# stm32f4stampV1_3.net
KiCad netlist of a schematic drawn in EAGLE
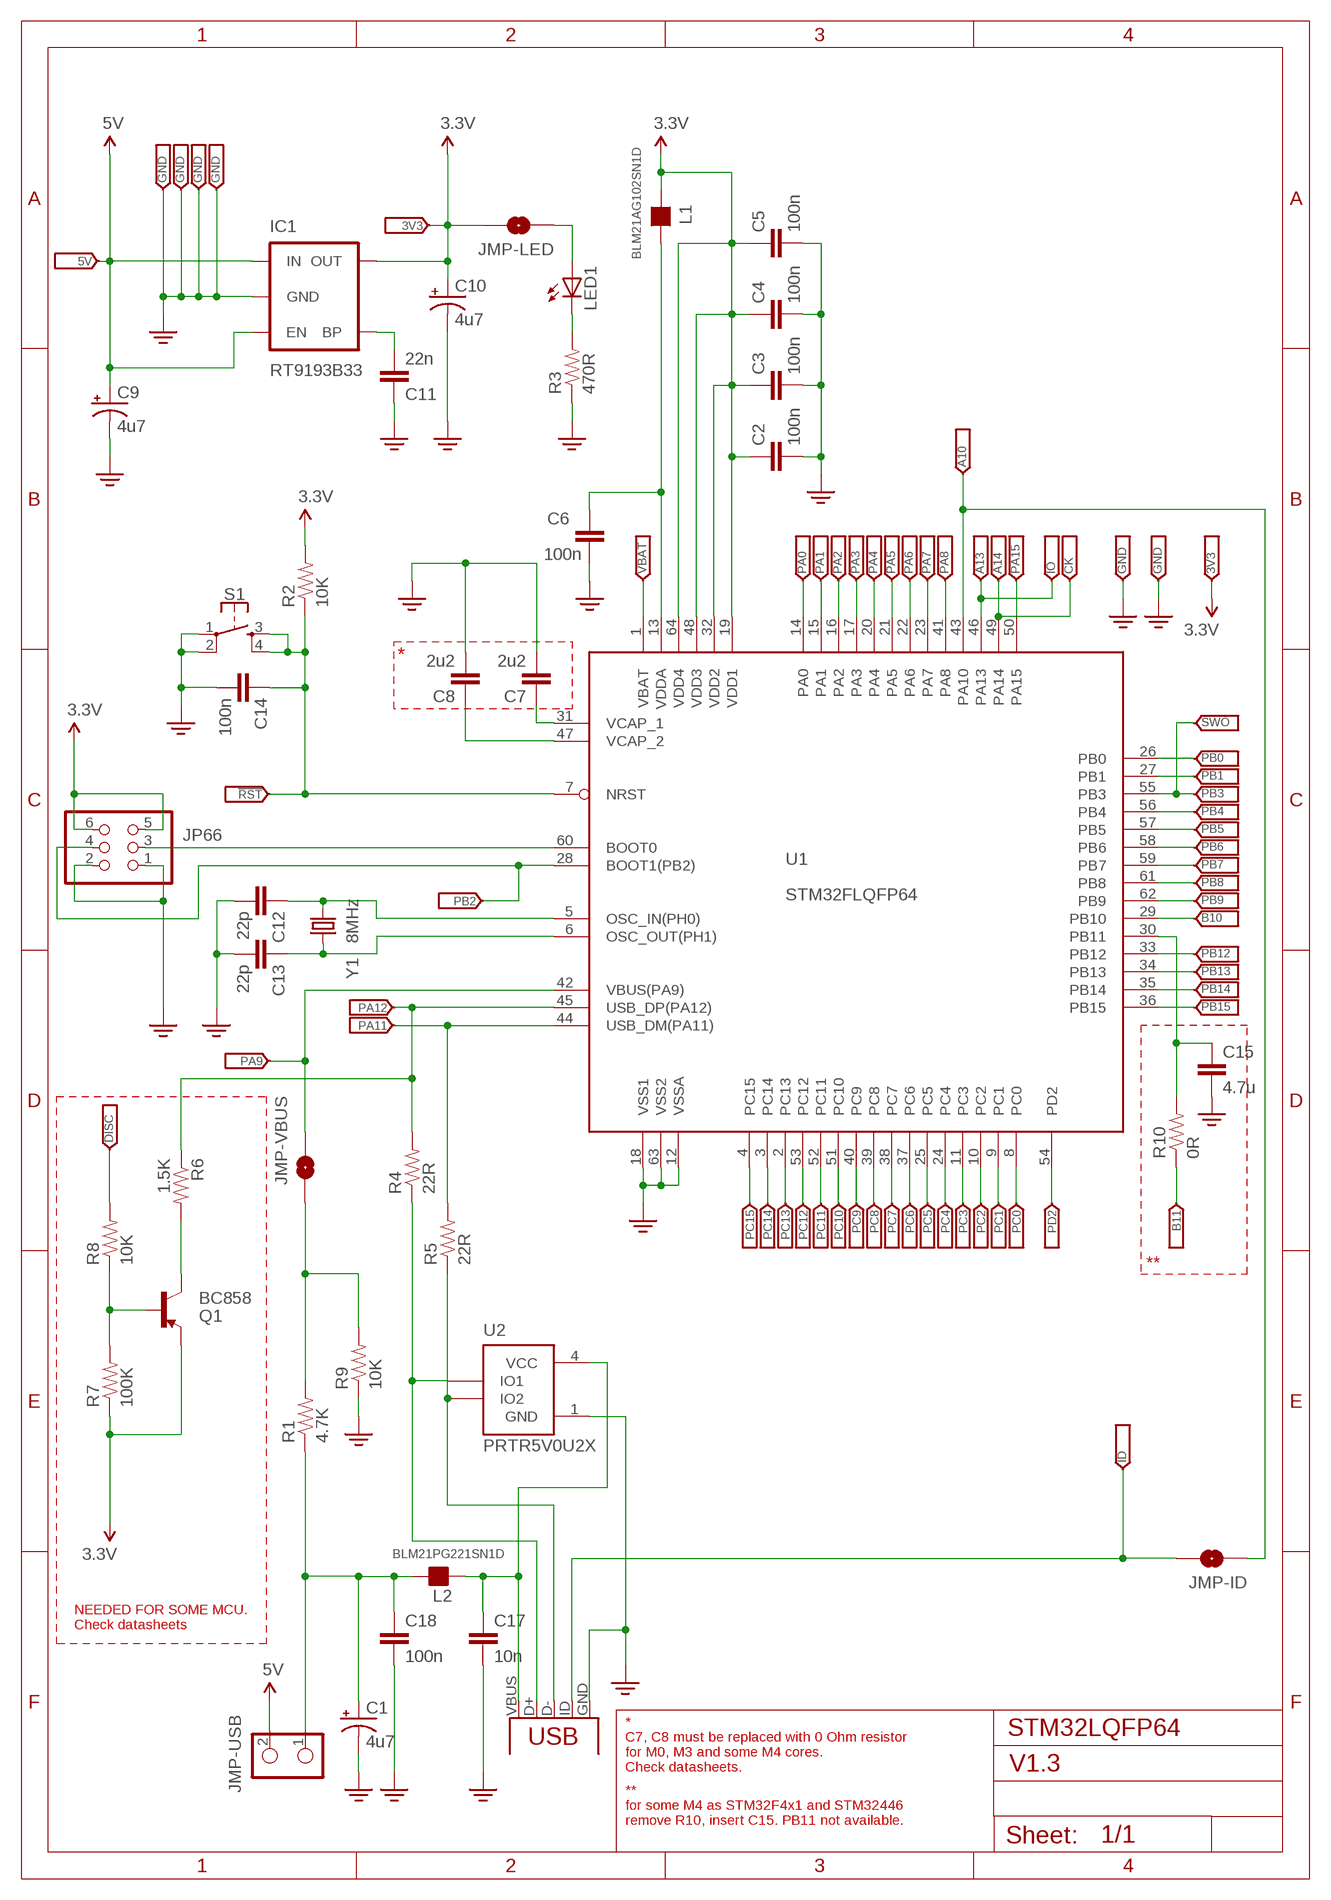
[diagram p0: schematic, sheet 1]

(export (version "E")
  (design (tool "Eeschema 10.0.6"))
  (components
    (comp (ref "C1")
      (value "4u7")
      (footprint "eagle-import:EIA3216-KIT")
      (libsource (lib "eagle-import") (part "CAP_POL1206-KIT"))
    )
    (comp (ref "C2")
      (value "100n")
      (footprint "eagle-import:0805")
      (libsource (lib "eagle-import") (part "CAP0805"))
    )
    (comp (ref "C3")
      (value "100n")
      (footprint "eagle-import:0805")
      (libsource (lib "eagle-import") (part "CAP0805"))
    )
    (comp (ref "C4")
      (value "100n")
      (footprint "eagle-import:0805")
      (libsource (lib "eagle-import") (part "CAP0805"))
    )
    (comp (ref "C5")
      (value "100n")
      (footprint "eagle-import:0805")
      (libsource (lib "eagle-import") (part "CAP0805"))
    )
    (comp (ref "C6")
      (value "100n")
      (footprint "eagle-import:0805")
      (libsource (lib "eagle-import") (part "CAP0805"))
    )
    (comp (ref "C7")
      (value "2u2")
      (footprint "eagle-import:0805")
      (libsource (lib "eagle-import") (part "CAP0805"))
    )
    (comp (ref "C8")
      (value "2u2")
      (footprint "eagle-import:0805")
      (libsource (lib "eagle-import") (part "CAP0805"))
    )
    (comp (ref "C9")
      (value "4u7")
      (footprint "eagle-import:EIA3216-KIT")
      (libsource (lib "eagle-import") (part "CAP_POL1206-KIT"))
    )
    (comp (ref "C10")
      (value "4u7")
      (footprint "eagle-import:EIA3216-KIT")
      (libsource (lib "eagle-import") (part "CAP_POL1206-KIT"))
    )
    (comp (ref "C11")
      (value "22n")
      (footprint "eagle-import:0805")
      (libsource (lib "eagle-import") (part "CAP0805"))
    )
    (comp (ref "C12")
      (value "22p")
      (footprint "eagle-import:0805")
      (libsource (lib "eagle-import") (part "CAP0805"))
    )
    (comp (ref "C13")
      (value "22p")
      (footprint "eagle-import:0805")
      (libsource (lib "eagle-import") (part "CAP0805"))
    )
    (comp (ref "C14")
      (value "100n")
      (footprint "eagle-import:0805")
      (libsource (lib "eagle-import") (part "CAP0805"))
    )
    (comp (ref "C15")
      (value "4.7u")
      (footprint "eagle-import:0805")
      (libsource (lib "eagle-import") (part "CAP0805"))
    )
    (comp (ref "C17")
      (value "10n")
      (footprint "eagle-import:0805")
      (libsource (lib "eagle-import") (part "CAP0805"))
    )
    (comp (ref "C18")
      (value "100n")
      (footprint "eagle-import:0805")
      (libsource (lib "eagle-import") (part "CAP0805"))
    )
    (comp (ref "IC1")
      (value "RT9193B33")
      (footprint "eagle-import:SOT23-5")
      (libsource (lib "eagle-import") (part "V_REG_LDOSMD"))
    )
    (comp (ref "JMP-ID")
      (value "SOLDERJUMPERNO")
      (footprint "eagle-import:SJ_2S-NO")
      (libsource (lib "eagle-import") (part "SOLDERJUMPERNO"))
    )
    (comp (ref "JMP-LED")
      (value "SOLDERJUMPERNO")
      (footprint "eagle-import:SJ_2S-NO")
      (libsource (lib "eagle-import") (part "SOLDERJUMPERNO"))
    )
    (comp (ref "JMP-USB")
      (value "JUMPER-2PTH")
      (footprint "eagle-import:1X02")
      (libsource (lib "eagle-import") (part "JUMPER-2PTH"))
    )
    (comp (ref "JMP-VBUS")
      (value "SOLDERJUMPERNO")
      (footprint "eagle-import:SJ_2S-NO")
      (libsource (lib "eagle-import") (part "SOLDERJUMPERNO"))
    )
    (comp (ref "JP1")
      (value "PA12")
      (footprint "eagle-import:1X1-HEADER-HOLE")
      (libsource (lib "eagle-import") (part "HEADERHOLE-HEADERHOLE"))
    )
    (comp (ref "JP2")
      (value "5V")
      (footprint "eagle-import:1X1-HEADER-HOLE")
      (libsource (lib "eagle-import") (part "HEADERHOLE-HEADERHOLE"))
    )
    (comp (ref "JP3")
      (value "GND")
      (footprint "eagle-import:1X1-HEADER-HOLE")
      (libsource (lib "eagle-import") (part "HEADERHOLE-HEADERHOLE"))
    )
    (comp (ref "JP4")
      (value "3V3")
      (footprint "eagle-import:1X1-HEADER-HOLE")
      (libsource (lib "eagle-import") (part "HEADERHOLE-HEADERHOLE"))
    )
    (comp (ref "JP5")
      (value "DISC")
      (footprint "eagle-import:1X1-HEADER-HOLE")
      (libsource (lib "eagle-import") (part "HEADERHOLE-HEADERHOLE"))
    )
    (comp (ref "JP6")
      (value "GND")
      (footprint "eagle-import:1X1-HEADER-HOLE")
      (libsource (lib "eagle-import") (part "HEADERHOLE-HEADERHOLE"))
    )
    (comp (ref "JP7")
      (value "GND")
      (footprint "eagle-import:1X1-HEADER-HOLE")
      (libsource (lib "eagle-import") (part "HEADERHOLE-HEADERHOLE"))
    )
    (comp (ref "JP8")
      (value "PB8")
      (footprint "eagle-import:1X1-HEADER-HOLE")
      (libsource (lib "eagle-import") (part "HEADERHOLE-HEADERHOLE"))
    )
    (comp (ref "JP9")
      (value "A10")
      (footprint "eagle-import:1X1-HEADER-HOLE")
      (libsource (lib "eagle-import") (part "HEADERHOLE-HEADERHOLE"))
    )
    (comp (ref "JP10")
      (value "PA8")
      (footprint "eagle-import:1X1-HEADER-HOLE")
      (libsource (lib "eagle-import") (part "HEADERHOLE-HEADERHOLE"))
    )
    (comp (ref "JP11")
      (value "A13")
      (footprint "eagle-import:1X1-HEADER-HOLE")
      (libsource (lib "eagle-import") (part "HEADERHOLE-HEADERHOLE"))
    )
    (comp (ref "JP12")
      (value "PC9")
      (footprint "eagle-import:1X1-HEADER-HOLE")
      (libsource (lib "eagle-import") (part "HEADERHOLE-HEADERHOLE"))
    )
    (comp (ref "JP13")
      (value "PC15")
      (footprint "eagle-import:1X1-HEADER-HOLE")
      (libsource (lib "eagle-import") (part "HEADERHOLE-HEADERHOLE"))
    )
    (comp (ref "JP14")
      (value "PC14")
      (footprint "eagle-import:1X1-HEADER-HOLE")
      (libsource (lib "eagle-import") (part "HEADERHOLE-HEADERHOLE"))
    )
    (comp (ref "JP15")
      (value "PC13")
      (footprint "eagle-import:1X1-HEADER-HOLE")
      (libsource (lib "eagle-import") (part "HEADERHOLE-HEADERHOLE"))
    )
    (comp (ref "JP16")
      (value "PC12")
      (footprint "eagle-import:1X1-HEADER-HOLE")
      (libsource (lib "eagle-import") (part "HEADERHOLE-HEADERHOLE"))
    )
    (comp (ref "JP17")
      (value "PC11")
      (footprint "eagle-import:1X1-HEADER-HOLE")
      (libsource (lib "eagle-import") (part "HEADERHOLE-HEADERHOLE"))
    )
    (comp (ref "JP18")
      (value "PC10")
      (footprint "eagle-import:1X1-HEADER-HOLE")
      (libsource (lib "eagle-import") (part "HEADERHOLE-HEADERHOLE"))
    )
    (comp (ref "JP19")
      (value "PC8")
      (footprint "eagle-import:1X1-HEADER-HOLE")
      (libsource (lib "eagle-import") (part "HEADERHOLE-HEADERHOLE"))
    )
    (comp (ref "JP20")
      (value "PC7")
      (footprint "eagle-import:1X1-HEADER-HOLE")
      (libsource (lib "eagle-import") (part "HEADERHOLE-HEADERHOLE"))
    )
    (comp (ref "JP21")
      (value "PC6")
      (footprint "eagle-import:1X1-HEADER-HOLE")
      (libsource (lib "eagle-import") (part "HEADERHOLE-HEADERHOLE"))
    )
    (comp (ref "JP22")
      (value "PC5")
      (footprint "eagle-import:1X1-HEADER-HOLE")
      (libsource (lib "eagle-import") (part "HEADERHOLE-HEADERHOLE"))
    )
    (comp (ref "JP23")
      (value "PC4")
      (footprint "eagle-import:1X1-HEADER-HOLE")
      (libsource (lib "eagle-import") (part "HEADERHOLE-HEADERHOLE"))
    )
    (comp (ref "JP24")
      (value "PC3")
      (footprint "eagle-import:1X1-HEADER-HOLE")
      (libsource (lib "eagle-import") (part "HEADERHOLE-HEADERHOLE"))
    )
    (comp (ref "JP25")
      (value "PC2")
      (footprint "eagle-import:1X1-HEADER-HOLE")
      (libsource (lib "eagle-import") (part "HEADERHOLE-HEADERHOLE"))
    )
    (comp (ref "JP26")
      (value "PC1")
      (footprint "eagle-import:1X1-HEADER-HOLE")
      (libsource (lib "eagle-import") (part "HEADERHOLE-HEADERHOLE"))
    )
    (comp (ref "JP27")
      (value "PC0")
      (footprint "eagle-import:1X1-HEADER-HOLE")
      (libsource (lib "eagle-import") (part "HEADERHOLE-HEADERHOLE"))
    )
    (comp (ref "JP28")
      (value "PD2")
      (footprint "eagle-import:1X1-HEADER-HOLE")
      (libsource (lib "eagle-import") (part "HEADERHOLE-HEADERHOLE"))
    )
    (comp (ref "JP29")
      (value "PA0")
      (footprint "eagle-import:1X1-HEADER-HOLE")
      (libsource (lib "eagle-import") (part "HEADERHOLE-HEADERHOLE"))
    )
    (comp (ref "JP30")
      (value "PA1")
      (footprint "eagle-import:1X1-HEADER-HOLE")
      (libsource (lib "eagle-import") (part "HEADERHOLE-HEADERHOLE"))
    )
    (comp (ref "JP31")
      (value "PA2")
      (footprint "eagle-import:1X1-HEADER-HOLE")
      (libsource (lib "eagle-import") (part "HEADERHOLE-HEADERHOLE"))
    )
    (comp (ref "JP32")
      (value "PA3")
      (footprint "eagle-import:1X1-HEADER-HOLE")
      (libsource (lib "eagle-import") (part "HEADERHOLE-HEADERHOLE"))
    )
    (comp (ref "JP33")
      (value "PA4")
      (footprint "eagle-import:1X1-HEADER-HOLE")
      (libsource (lib "eagle-import") (part "HEADERHOLE-HEADERHOLE"))
    )
    (comp (ref "JP34")
      (value "PA5")
      (footprint "eagle-import:1X1-HEADER-HOLE")
      (libsource (lib "eagle-import") (part "HEADERHOLE-HEADERHOLE"))
    )
    (comp (ref "JP35")
      (value "PA6")
      (footprint "eagle-import:1X1-HEADER-HOLE")
      (libsource (lib "eagle-import") (part "HEADERHOLE-HEADERHOLE"))
    )
    (comp (ref "JP36")
      (value "PA7")
      (footprint "eagle-import:1X1-HEADER-HOLE")
      (libsource (lib "eagle-import") (part "HEADERHOLE-HEADERHOLE"))
    )
    (comp (ref "JP37")
      (value "A14")
      (footprint "eagle-import:1X1-HEADER-HOLE")
      (libsource (lib "eagle-import") (part "HEADERHOLE-HEADERHOLE"))
    )
    (comp (ref "JP38")
      (value "PA15")
      (footprint "eagle-import:1X1-HEADER-HOLE")
      (libsource (lib "eagle-import") (part "HEADERHOLE-HEADERHOLE"))
    )
    (comp (ref "JP39")
      (value "PB0")
      (footprint "eagle-import:1X1-HEADER-HOLE")
      (libsource (lib "eagle-import") (part "HEADERHOLE-HEADERHOLE"))
    )
    (comp (ref "JP40")
      (value "PB1")
      (footprint "eagle-import:1X1-HEADER-HOLE")
      (libsource (lib "eagle-import") (part "HEADERHOLE-HEADERHOLE"))
    )
    (comp (ref "JP41")
      (value "PB3")
      (footprint "eagle-import:1X1-HEADER-HOLE")
      (libsource (lib "eagle-import") (part "HEADERHOLE-HEADERHOLE"))
    )
    (comp (ref "JP42")
      (value "PB4")
      (footprint "eagle-import:1X1-HEADER-HOLE")
      (libsource (lib "eagle-import") (part "HEADERHOLE-HEADERHOLE"))
    )
    (comp (ref "JP43")
      (value "PB5")
      (footprint "eagle-import:1X1-HEADER-HOLE")
      (libsource (lib "eagle-import") (part "HEADERHOLE-HEADERHOLE"))
    )
    (comp (ref "JP44")
      (value "PB6")
      (footprint "eagle-import:1X1-HEADER-HOLE")
      (libsource (lib "eagle-import") (part "HEADERHOLE-HEADERHOLE"))
    )
    (comp (ref "JP45")
      (value "PB7")
      (footprint "eagle-import:1X1-HEADER-HOLE")
      (libsource (lib "eagle-import") (part "HEADERHOLE-HEADERHOLE"))
    )
    (comp (ref "JP46")
      (value "PB9")
      (footprint "eagle-import:1X1-HEADER-HOLE")
      (libsource (lib "eagle-import") (part "HEADERHOLE-HEADERHOLE"))
    )
    (comp (ref "JP47")
      (value "B10")
      (footprint "eagle-import:1X1-HEADER-HOLE")
      (libsource (lib "eagle-import") (part "HEADERHOLE-HEADERHOLE"))
    )
    (comp (ref "JP48")
      (value "B11")
      (footprint "eagle-import:1X1-HEADER-HOLE")
      (libsource (lib "eagle-import") (part "HEADERHOLE-HEADERHOLE"))
    )
    (comp (ref "JP49")
      (value "PB12")
      (footprint "eagle-import:1X1-HEADER-HOLE")
      (libsource (lib "eagle-import") (part "HEADERHOLE-HEADERHOLE"))
    )
    (comp (ref "JP50")
      (value "PB13")
      (footprint "eagle-import:1X1-HEADER-HOLE")
      (libsource (lib "eagle-import") (part "HEADERHOLE-HEADERHOLE"))
    )
    (comp (ref "JP51")
      (value "PB14")
      (footprint "eagle-import:1X1-HEADER-HOLE")
      (libsource (lib "eagle-import") (part "HEADERHOLE-HEADERHOLE"))
    )
    (comp (ref "JP52")
      (value "PB15")
      (footprint "eagle-import:1X1-HEADER-HOLE")
      (libsource (lib "eagle-import") (part "HEADERHOLE-HEADERHOLE"))
    )
    (comp (ref "JP53")
      (value "VBAT")
      (footprint "eagle-import:1X1-HEADER-HOLE")
      (libsource (lib "eagle-import") (part "HEADERHOLE-HEADERHOLE"))
    )
    (comp (ref "JP54")
      (value "!RST")
      (footprint "eagle-import:1X1-HEADER-HOLE")
      (libsource (lib "eagle-import") (part "HEADERHOLE-HEADERHOLE"))
    )
    (comp (ref "JP55")
      (value "GND")
      (footprint "eagle-import:1X1-HEADER-HOLE")
      (libsource (lib "eagle-import") (part "HEADERHOLE-HEADERHOLE"))
    )
    (comp (ref "JP56")
      (value "ID")
      (footprint "eagle-import:1X1-HEADER-HOLE")
      (libsource (lib "eagle-import") (part "HEADERHOLE-HEADERHOLE"))
    )
    (comp (ref "JP57")
      (value "PB2")
      (footprint "eagle-import:1X1-HEADER-HOLE")
      (libsource (lib "eagle-import") (part "HEADERHOLE-HEADERHOLE"))
    )
    (comp (ref "JP58")
      (value "PA11")
      (footprint "eagle-import:1X1-HEADER-HOLE")
      (libsource (lib "eagle-import") (part "HEADERHOLE-HEADERHOLE"))
    )
    (comp (ref "JP59")
      (value "IO")
      (footprint "eagle-import:1X1-HEADER-HOLE")
      (libsource (lib "eagle-import") (part "HEADERHOLE-HEADERHOLE"))
    )
    (comp (ref "JP60")
      (value "CK")
      (footprint "eagle-import:1X1-HEADER-HOLE")
      (libsource (lib "eagle-import") (part "HEADERHOLE-HEADERHOLE"))
    )
    (comp (ref "JP61")
      (value "SWO")
      (footprint "eagle-import:1X1-HEADER-HOLE")
      (libsource (lib "eagle-import") (part "HEADERHOLE-HEADERHOLE"))
    )
    (comp (ref "JP62")
      (value "GND")
      (footprint "eagle-import:1X1-HEADER-HOLE")
      (libsource (lib "eagle-import") (part "HEADERHOLE-HEADERHOLE"))
    )
    (comp (ref "JP63")
      (value "3V3")
      (footprint "eagle-import:1X1-HEADER-HOLE")
      (libsource (lib "eagle-import") (part "HEADERHOLE-HEADERHOLE"))
    )
    (comp (ref "JP64")
      (value "PA9")
      (footprint "eagle-import:1X1-HEADER-HOLE")
      (libsource (lib "eagle-import") (part "HEADERHOLE-HEADERHOLE"))
    )
    (comp (ref "JP65")
      (value "GND")
      (footprint "eagle-import:1X1-HEADER-HOLE")
      (libsource (lib "eagle-import") (part "HEADERHOLE-HEADERHOLE"))
    )
    (comp (ref "JP66")
      (value "PINHD-2X3")
      (footprint "eagle-import:2X03")
      (libsource (lib "eagle-import") (part "PINHD-2X3"))
    )
    (comp (ref "L1")
      (value "BLM21AG102SN1D")
      (footprint "eagle-import:L0805")
      (libsource (lib "eagle-import") (part "FB_0805"))
    )
    (comp (ref "L2")
      (value "BLM21PG221SN1D")
      (footprint "eagle-import:L0805")
      (libsource (lib "eagle-import") (part "FB_0805"))
    )
    (comp (ref "LED1")
      (value "LEDSML0805")
      (footprint "eagle-import:SML0805")
      (libsource (lib "eagle-import") (part "LEDSML0805"))
    )
    (comp (ref "Q1")
      (value "BC858")
      (footprint "eagle-import:SOT23-3")
      (libsource (lib "eagle-import") (part "TRANSISTOR_PNPSMD"))
    )
    (comp (ref "R1")
      (value "4.7K")
      (footprint "eagle-import:0805")
      (libsource (lib "eagle-import") (part "RESISTOR0805-RES"))
    )
    (comp (ref "R2")
      (value "10K")
      (footprint "eagle-import:0805")
      (libsource (lib "eagle-import") (part "RESISTOR0805-RES"))
    )
    (comp (ref "R3")
      (value "470R")
      (footprint "eagle-import:0805")
      (libsource (lib "eagle-import") (part "RESISTOR0805-RES"))
    )
    (comp (ref "R4")
      (value "22R")
      (footprint "eagle-import:0805")
      (libsource (lib "eagle-import") (part "RESISTOR0805-RES"))
    )
    (comp (ref "R5")
      (value "22R")
      (footprint "eagle-import:0805")
      (libsource (lib "eagle-import") (part "RESISTOR0805-RES"))
    )
    (comp (ref "R6")
      (value "1.5K")
      (footprint "eagle-import:0805")
      (libsource (lib "eagle-import") (part "RESISTOR0805-RES"))
    )
    (comp (ref "R7")
      (value "100K")
      (footprint "eagle-import:0805")
      (libsource (lib "eagle-import") (part "RESISTOR0805-RES"))
    )
    (comp (ref "R8")
      (value "10K")
      (footprint "eagle-import:0805")
      (libsource (lib "eagle-import") (part "RESISTOR0805-RES"))
    )
    (comp (ref "R9")
      (value "10K")
      (footprint "eagle-import:0805")
      (libsource (lib "eagle-import") (part "RESISTOR0805-RES"))
    )
    (comp (ref "R10")
      (value "0R")
      (footprint "eagle-import:0805")
      (libsource (lib "eagle-import") (part "RESISTOR0805-RES"))
    )
    (comp (ref "S1")
      (value "MOMENTARY-SWITCH-SPST-2-SMD-5.2MM")
      (footprint "eagle-import:TACTILE_SWITCH_SMD_5.2MM")
      (libsource (lib "eagle-import") (part "MOMENTARY-SWITCH-SPST-2-SMD-5.2MM"))
    )
    (comp (ref "U1")
      (value "STM32FLQFP64")
      (footprint "eagle-import:LQFP64")
      (libsource (lib "eagle-import") (part "STM32F405RGT"))
    )
    (comp (ref "U2")
      (value "PRTR5V0U2X")
      (footprint "eagle-import:SOT-143B")
      (fields
        (field (name "MANUFACTURER") "NXP Semiconductors")
        (field (name "PART_NUMBER") "PRTR5V0U2X,215")
      )
      (libsource (lib "eagle-import") (part "PRTR5V0U2X?"))
    )
    (comp (ref "USB")
      (value "USB-MICROB-SMD")
      (footprint "eagle-import:USB-MICROB-SMD")
      (libsource (lib "eagle-import") (part "USB-MICROB-SMD"))
    )
    (comp (ref "Y1")
      (value "8MHz")
      (footprint "eagle-import:CRYSTAL-SMD-5X3")
      (libsource (lib "eagle-import") (part "CRYSTAL5X3"))
    )
  )
  (nets
    (net (code "1") (name "3.3V") (class "Default")
      (node (ref "C10") (pin "A") (pinfunction "+_A") (pintype "passive"))
      (node (ref "C2") (pin "1") (pinfunction "1_1") (pintype "passive"))
      (node (ref "C3") (pin "1") (pinfunction "1_1") (pintype "passive"))
      (node (ref "C4") (pin "1") (pinfunction "1_1") (pintype "passive"))
      (node (ref "C5") (pin "1") (pinfunction "1_1") (pintype "passive"))
      (node (ref "IC1") (pin "5") (pinfunction "OUT_5") (pintype "passive"))
      (node (ref "JMP-LED") (pin "2") (pinfunction "2_2") (pintype "passive"))
      (node (ref "JP4") (pin "1") (pinfunction "P$1_1") (pintype "bidirectional"))
      (node (ref "JP63") (pin "1") (pinfunction "P$1_1") (pintype "bidirectional"))
      (node (ref "JP66") (pin "5") (pinfunction "5_5") (pintype "passive"))
      (node (ref "JP66") (pin "6") (pinfunction "6_6") (pintype "passive"))
      (node (ref "L1") (pin "2") (pinfunction "2_2") (pintype "passive"))
      (node (ref "Q1") (pin "2") (pinfunction "E_2") (pintype "passive"))
      (node (ref "R2") (pin "2") (pinfunction "2_2") (pintype "passive"))
      (node (ref "R7") (pin "1") (pinfunction "1_1") (pintype "passive"))
      (node (ref "U1") (pin "19") (pinfunction "VDD1_19") (pintype "power_in"))
      (node (ref "U1") (pin "32") (pinfunction "VDD2_32") (pintype "power_in"))
      (node (ref "U1") (pin "48") (pinfunction "VDD3_48") (pintype "power_in"))
      (node (ref "U1") (pin "64") (pinfunction "VDD4_64") (pintype "power_in"))
    )
    (net (code "2") (name "5V") (class "Default")
      (node (ref "C9") (pin "A") (pinfunction "+_A") (pintype "passive"))
      (node (ref "IC1") (pin "1") (pinfunction "IN_1") (pintype "input"))
      (node (ref "IC1") (pin "3") (pinfunction "EN_3") (pintype "input"))
      (node (ref "JMP-USB") (pin "2") (pinfunction "2_2") (pintype "passive"))
      (node (ref "JP2") (pin "1") (pinfunction "P$1_1") (pintype "bidirectional"))
    )
    (net (code "3") (name "GND") (class "Default")
      (node (ref "C1") (pin "C") (pinfunction "-_C") (pintype "passive"))
      (node (ref "C10") (pin "C") (pinfunction "-_C") (pintype "passive"))
      (node (ref "C11") (pin "1") (pinfunction "1_1") (pintype "passive"))
      (node (ref "C12") (pin "2") (pinfunction "2_2") (pintype "passive"))
      (node (ref "C13") (pin "2") (pinfunction "2_2") (pintype "passive"))
      (node (ref "C14") (pin "2") (pinfunction "2_2") (pintype "passive"))
      (node (ref "C15") (pin "2") (pinfunction "2_2") (pintype "passive"))
      (node (ref "C17") (pin "2") (pinfunction "2_2") (pintype "passive"))
      (node (ref "C18") (pin "2") (pinfunction "2_2") (pintype "passive"))
      (node (ref "C2") (pin "2") (pinfunction "2_2") (pintype "passive"))
      (node (ref "C3") (pin "2") (pinfunction "2_2") (pintype "passive"))
      (node (ref "C4") (pin "2") (pinfunction "2_2") (pintype "passive"))
      (node (ref "C5") (pin "2") (pinfunction "2_2") (pintype "passive"))
      (node (ref "C6") (pin "2") (pinfunction "2_2") (pintype "passive"))
      (node (ref "C7") (pin "2") (pinfunction "2_2") (pintype "passive"))
      (node (ref "C8") (pin "2") (pinfunction "2_2") (pintype "passive"))
      (node (ref "C9") (pin "C") (pinfunction "-_C") (pintype "passive"))
      (node (ref "IC1") (pin "2") (pinfunction "GND_2") (pintype "input"))
      (node (ref "JP3") (pin "1") (pinfunction "P$1_1") (pintype "bidirectional"))
      (node (ref "JP55") (pin "1") (pinfunction "P$1_1") (pintype "bidirectional"))
      (node (ref "JP6") (pin "1") (pinfunction "P$1_1") (pintype "bidirectional"))
      (node (ref "JP62") (pin "1") (pinfunction "P$1_1") (pintype "bidirectional"))
      (node (ref "JP65") (pin "1") (pinfunction "P$1_1") (pintype "bidirectional"))
      (node (ref "JP66") (pin "1") (pinfunction "1_1") (pintype "passive"))
      (node (ref "JP66") (pin "2") (pinfunction "2_2") (pintype "passive"))
      (node (ref "JP7") (pin "1") (pinfunction "P$1_1") (pintype "bidirectional"))
      (node (ref "R3") (pin "1") (pinfunction "1_1") (pintype "passive"))
      (node (ref "R9") (pin "1") (pinfunction "1_1") (pintype "passive"))
      (node (ref "S1") (pin "1") (pinfunction "1_1") (pintype "passive"))
      (node (ref "S1") (pin "2") (pinfunction "2_2") (pintype "passive"))
      (node (ref "U1") (pin "12") (pinfunction "VSSA_12") (pintype "power_in"))
      (node (ref "U1") (pin "18") (pinfunction "VSS1_18") (pintype "power_in"))
      (node (ref "U1") (pin "63") (pinfunction "VSS2_63") (pintype "power_in"))
      (node (ref "U2") (pin "1") (pinfunction "GND_1") (pintype "bidirectional"))
      (node (ref "USB") (pin "GND") (pinfunction "GND_GND") (pintype "bidirectional"))
      (node (ref "USB") (pin "MT1") (pinfunction "P$1_MT1") (pintype "bidirectional"))
      (node (ref "USB") (pin "MT2") (pinfunction "P$1_MT2") (pintype "bidirectional"))
      (node (ref "USB") (pin "MT3") (pinfunction "P$1_MT3") (pintype "bidirectional"))
      (node (ref "USB") (pin "MT4") (pinfunction "P$1_MT4") (pintype "bidirectional"))
    )
    (net (code "4") (name "Net-(C1-+)") (class "Default")
      (node (ref "C1") (pin "A") (pinfunction "+_A") (pintype "passive"))
      (node (ref "C18") (pin "1") (pinfunction "1_1") (pintype "passive"))
      (node (ref "JMP-USB") (pin "1") (pinfunction "1_1") (pintype "passive"))
      (node (ref "L2") (pin "2") (pinfunction "2_2") (pintype "passive"))
      (node (ref "R1") (pin "1") (pinfunction "1_1") (pintype "passive"))
    )
    (net (code "5") (name "Net-(IC1-BP)") (class "Default")
      (node (ref "C11") (pin "2") (pinfunction "2_2") (pintype "passive"))
      (node (ref "IC1") (pin "4") (pinfunction "BP_4") (pintype "input"))
    )
    (net (code "6") (name "Net-(JMP-LED-Pad1)") (class "Default")
      (node (ref "JMP-LED") (pin "1") (pinfunction "1_1") (pintype "passive"))
      (node (ref "LED1") (pin "A") (pinfunction "A_A") (pintype "passive"))
    )
    (net (code "7") (name "Net-(JMP-VBUS-Pad1)") (class "Default")
      (node (ref "JMP-VBUS") (pin "1") (pinfunction "1_1") (pintype "passive"))
      (node (ref "R1") (pin "2") (pinfunction "2_2") (pintype "passive"))
      (node (ref "R9") (pin "2") (pinfunction "2_2") (pintype "passive"))
    )
    (net (code "8") (name "Net-(JP1-P$1)") (class "Default")
      (node (ref "JP1") (pin "1") (pinfunction "P$1_1") (pintype "bidirectional"))
      (node (ref "R4") (pin "2") (pinfunction "2_2") (pintype "passive"))
      (node (ref "R6") (pin "1") (pinfunction "1_1") (pintype "passive"))
      (node (ref "U1") (pin "45") (pinfunction "USB_DP(PA12)_45") (pintype "bidirectional"))
    )
    (net (code "9") (name "Net-(JP5-P$1)") (class "Default")
      (node (ref "JP5") (pin "1") (pinfunction "P$1_1") (pintype "bidirectional"))
      (node (ref "R8") (pin "2") (pinfunction "2_2") (pintype "passive"))
    )
    (net (code "10") (name "Net-(JP8-P$1)") (class "Default")
      (node (ref "JP8") (pin "1") (pinfunction "P$1_1") (pintype "bidirectional"))
      (node (ref "U1") (pin "61") (pinfunction "PB8_61") (pintype "bidirectional"))
    )
    (net (code "11") (name "Net-(JP9-P$1)") (class "Default")
      (node (ref "JMP-ID") (pin "1") (pinfunction "1_1") (pintype "passive"))
      (node (ref "JP9") (pin "1") (pinfunction "P$1_1") (pintype "bidirectional"))
      (node (ref "U1") (pin "43") (pinfunction "PA10_43") (pintype "bidirectional"))
    )
    (net (code "12") (name "Net-(JP10-P$1)") (class "Default")
      (node (ref "JP10") (pin "1") (pinfunction "P$1_1") (pintype "bidirectional"))
      (node (ref "U1") (pin "41") (pinfunction "PA8_41") (pintype "bidirectional"))
    )
    (net (code "13") (name "Net-(JP11-P$1)") (class "Default")
      (node (ref "JP11") (pin "1") (pinfunction "P$1_1") (pintype "bidirectional"))
      (node (ref "JP59") (pin "1") (pinfunction "P$1_1") (pintype "bidirectional"))
      (node (ref "U1") (pin "46") (pinfunction "PA13_46") (pintype "bidirectional"))
    )
    (net (code "14") (name "Net-(JP12-P$1)") (class "Default")
      (node (ref "JP12") (pin "1") (pinfunction "P$1_1") (pintype "bidirectional"))
      (node (ref "U1") (pin "40") (pinfunction "PC9_40") (pintype "bidirectional"))
    )
    (net (code "15") (name "Net-(JP13-P$1)") (class "Default")
      (node (ref "JP13") (pin "1") (pinfunction "P$1_1") (pintype "bidirectional"))
      (node (ref "U1") (pin "4") (pinfunction "PC15_4") (pintype "bidirectional"))
    )
    (net (code "16") (name "Net-(JP14-P$1)") (class "Default")
      (node (ref "JP14") (pin "1") (pinfunction "P$1_1") (pintype "bidirectional"))
      (node (ref "U1") (pin "3") (pinfunction "PC14_3") (pintype "bidirectional"))
    )
    (net (code "17") (name "Net-(JP15-P$1)") (class "Default")
      (node (ref "JP15") (pin "1") (pinfunction "P$1_1") (pintype "bidirectional"))
      (node (ref "U1") (pin "2") (pinfunction "PC13_2") (pintype "bidirectional"))
    )
    (net (code "18") (name "Net-(JP16-P$1)") (class "Default")
      (node (ref "JP16") (pin "1") (pinfunction "P$1_1") (pintype "bidirectional"))
      (node (ref "U1") (pin "53") (pinfunction "PC12_53") (pintype "bidirectional"))
    )
    (net (code "19") (name "Net-(JP17-P$1)") (class "Default")
      (node (ref "JP17") (pin "1") (pinfunction "P$1_1") (pintype "bidirectional"))
      (node (ref "U1") (pin "52") (pinfunction "PC11_52") (pintype "bidirectional"))
    )
    (net (code "20") (name "Net-(JP18-P$1)") (class "Default")
      (node (ref "JP18") (pin "1") (pinfunction "P$1_1") (pintype "bidirectional"))
      (node (ref "U1") (pin "51") (pinfunction "PC10_51") (pintype "bidirectional"))
    )
    (net (code "21") (name "Net-(JP19-P$1)") (class "Default")
      (node (ref "JP19") (pin "1") (pinfunction "P$1_1") (pintype "bidirectional"))
      (node (ref "U1") (pin "39") (pinfunction "PC8_39") (pintype "bidirectional"))
    )
    (net (code "22") (name "Net-(JP20-P$1)") (class "Default")
      (node (ref "JP20") (pin "1") (pinfunction "P$1_1") (pintype "bidirectional"))
      (node (ref "U1") (pin "38") (pinfunction "PC7_38") (pintype "bidirectional"))
    )
    (net (code "23") (name "Net-(JP21-P$1)") (class "Default")
      (node (ref "JP21") (pin "1") (pinfunction "P$1_1") (pintype "bidirectional"))
      (node (ref "U1") (pin "37") (pinfunction "PC6_37") (pintype "bidirectional"))
    )
    (net (code "24") (name "Net-(JP22-P$1)") (class "Default")
      (node (ref "JP22") (pin "1") (pinfunction "P$1_1") (pintype "bidirectional"))
      (node (ref "U1") (pin "25") (pinfunction "PC5_25") (pintype "bidirectional"))
    )
    (net (code "25") (name "Net-(JP23-P$1)") (class "Default")
      (node (ref "JP23") (pin "1") (pinfunction "P$1_1") (pintype "bidirectional"))
      (node (ref "U1") (pin "24") (pinfunction "PC4_24") (pintype "bidirectional"))
    )
    (net (code "26") (name "Net-(JP24-P$1)") (class "Default")
      (node (ref "JP24") (pin "1") (pinfunction "P$1_1") (pintype "bidirectional"))
      (node (ref "U1") (pin "11") (pinfunction "PC3_11") (pintype "bidirectional"))
    )
    (net (code "27") (name "Net-(JP25-P$1)") (class "Default")
      (node (ref "JP25") (pin "1") (pinfunction "P$1_1") (pintype "bidirectional"))
      (node (ref "U1") (pin "10") (pinfunction "PC2_10") (pintype "bidirectional"))
    )
    (net (code "28") (name "Net-(JP26-P$1)") (class "Default")
      (node (ref "JP26") (pin "1") (pinfunction "P$1_1") (pintype "bidirectional"))
      (node (ref "U1") (pin "9") (pinfunction "PC1_9") (pintype "bidirectional"))
    )
    (net (code "29") (name "Net-(JP27-P$1)") (class "Default")
      (node (ref "JP27") (pin "1") (pinfunction "P$1_1") (pintype "bidirectional"))
      (node (ref "U1") (pin "8") (pinfunction "PC0_8") (pintype "bidirectional"))
    )
    (net (code "30") (name "Net-(JP28-P$1)") (class "Default")
      (node (ref "JP28") (pin "1") (pinfunction "P$1_1") (pintype "bidirectional"))
      (node (ref "U1") (pin "54") (pinfunction "PD2_54") (pintype "bidirectional"))
    )
    (net (code "31") (name "Net-(JP29-P$1)") (class "Default")
      (node (ref "JP29") (pin "1") (pinfunction "P$1_1") (pintype "bidirectional"))
      (node (ref "U1") (pin "14") (pinfunction "PA0_14") (pintype "bidirectional"))
    )
    (net (code "32") (name "Net-(JP30-P$1)") (class "Default")
      (node (ref "JP30") (pin "1") (pinfunction "P$1_1") (pintype "bidirectional"))
      (node (ref "U1") (pin "15") (pinfunction "PA1_15") (pintype "bidirectional"))
    )
    (net (code "33") (name "Net-(JP31-P$1)") (class "Default")
      (node (ref "JP31") (pin "1") (pinfunction "P$1_1") (pintype "bidirectional"))
      (node (ref "U1") (pin "16") (pinfunction "PA2_16") (pintype "bidirectional"))
    )
    (net (code "34") (name "Net-(JP32-P$1)") (class "Default")
      (node (ref "JP32") (pin "1") (pinfunction "P$1_1") (pintype "bidirectional"))
      (node (ref "U1") (pin "17") (pinfunction "PA3_17") (pintype "bidirectional"))
    )
    (net (code "35") (name "Net-(JP33-P$1)") (class "Default")
      (node (ref "JP33") (pin "1") (pinfunction "P$1_1") (pintype "bidirectional"))
      (node (ref "U1") (pin "20") (pinfunction "PA4_20") (pintype "bidirectional"))
    )
    (net (code "36") (name "Net-(JP34-P$1)") (class "Default")
      (node (ref "JP34") (pin "1") (pinfunction "P$1_1") (pintype "bidirectional"))
      (node (ref "U1") (pin "21") (pinfunction "PA5_21") (pintype "bidirectional"))
    )
    (net (code "37") (name "Net-(JP35-P$1)") (class "Default")
      (node (ref "JP35") (pin "1") (pinfunction "P$1_1") (pintype "bidirectional"))
      (node (ref "U1") (pin "22") (pinfunction "PA6_22") (pintype "bidirectional"))
    )
    (net (code "38") (name "Net-(JP36-P$1)") (class "Default")
      (node (ref "JP36") (pin "1") (pinfunction "P$1_1") (pintype "bidirectional"))
      (node (ref "U1") (pin "23") (pinfunction "PA7_23") (pintype "bidirectional"))
    )
    (net (code "39") (name "Net-(JP37-P$1)") (class "Default")
      (node (ref "JP37") (pin "1") (pinfunction "P$1_1") (pintype "bidirectional"))
      (node (ref "JP60") (pin "1") (pinfunction "P$1_1") (pintype "bidirectional"))
      (node (ref "U1") (pin "49") (pinfunction "PA14_49") (pintype "bidirectional"))
    )
    (net (code "40") (name "Net-(JP38-P$1)") (class "Default")
      (node (ref "JP38") (pin "1") (pinfunction "P$1_1") (pintype "bidirectional"))
      (node (ref "U1") (pin "50") (pinfunction "PA15_50") (pintype "bidirectional"))
    )
    (net (code "41") (name "Net-(JP39-P$1)") (class "Default")
      (node (ref "JP39") (pin "1") (pinfunction "P$1_1") (pintype "bidirectional"))
      (node (ref "U1") (pin "26") (pinfunction "PB0_26") (pintype "bidirectional"))
    )
    (net (code "42") (name "Net-(JP40-P$1)") (class "Default")
      (node (ref "JP40") (pin "1") (pinfunction "P$1_1") (pintype "bidirectional"))
      (node (ref "U1") (pin "27") (pinfunction "PB1_27") (pintype "bidirectional"))
    )
    (net (code "43") (name "Net-(JP41-P$1)") (class "Default")
      (node (ref "JP41") (pin "1") (pinfunction "P$1_1") (pintype "bidirectional"))
      (node (ref "JP61") (pin "1") (pinfunction "P$1_1") (pintype "bidirectional"))
      (node (ref "U1") (pin "55") (pinfunction "PB3_55") (pintype "bidirectional"))
    )
    (net (code "44") (name "Net-(JP42-P$1)") (class "Default")
      (node (ref "JP42") (pin "1") (pinfunction "P$1_1") (pintype "bidirectional"))
      (node (ref "U1") (pin "56") (pinfunction "PB4_56") (pintype "bidirectional"))
    )
    (net (code "45") (name "Net-(JP43-P$1)") (class "Default")
      (node (ref "JP43") (pin "1") (pinfunction "P$1_1") (pintype "bidirectional"))
      (node (ref "U1") (pin "57") (pinfunction "PB5_57") (pintype "bidirectional"))
    )
    (net (code "46") (name "Net-(JP44-P$1)") (class "Default")
      (node (ref "JP44") (pin "1") (pinfunction "P$1_1") (pintype "bidirectional"))
      (node (ref "U1") (pin "58") (pinfunction "PB6_58") (pintype "bidirectional"))
    )
    (net (code "47") (name "Net-(JP45-P$1)") (class "Default")
      (node (ref "JP45") (pin "1") (pinfunction "P$1_1") (pintype "bidirectional"))
      (node (ref "U1") (pin "59") (pinfunction "PB7_59") (pintype "bidirectional"))
    )
    (net (code "48") (name "Net-(JP46-P$1)") (class "Default")
      (node (ref "JP46") (pin "1") (pinfunction "P$1_1") (pintype "bidirectional"))
      (node (ref "U1") (pin "62") (pinfunction "PB9_62") (pintype "bidirectional"))
    )
    (net (code "49") (name "Net-(JP47-P$1)") (class "Default")
      (node (ref "JP47") (pin "1") (pinfunction "P$1_1") (pintype "bidirectional"))
      (node (ref "U1") (pin "29") (pinfunction "PB10_29") (pintype "bidirectional"))
    )
    (net (code "50") (name "Net-(JP48-P$1)") (class "Default")
      (node (ref "JP48") (pin "1") (pinfunction "P$1_1") (pintype "bidirectional"))
      (node (ref "R10") (pin "1") (pinfunction "1_1") (pintype "passive"))
    )
    (net (code "51") (name "Net-(JP49-P$1)") (class "Default")
      (node (ref "JP49") (pin "1") (pinfunction "P$1_1") (pintype "bidirectional"))
      (node (ref "U1") (pin "33") (pinfunction "PB12_33") (pintype "bidirectional"))
    )
    (net (code "52") (name "Net-(JP50-P$1)") (class "Default")
      (node (ref "JP50") (pin "1") (pinfunction "P$1_1") (pintype "bidirectional"))
      (node (ref "U1") (pin "34") (pinfunction "PB13_34") (pintype "bidirectional"))
    )
    (net (code "53") (name "Net-(JP51-P$1)") (class "Default")
      (node (ref "JP51") (pin "1") (pinfunction "P$1_1") (pintype "bidirectional"))
      (node (ref "U1") (pin "35") (pinfunction "PB14_35") (pintype "bidirectional"))
    )
    (net (code "54") (name "Net-(JP52-P$1)") (class "Default")
      (node (ref "JP52") (pin "1") (pinfunction "P$1_1") (pintype "bidirectional"))
      (node (ref "U1") (pin "36") (pinfunction "PB15_36") (pintype "bidirectional"))
    )
    (net (code "55") (name "Net-(JP53-P$1)") (class "Default")
      (node (ref "JP53") (pin "1") (pinfunction "P$1_1") (pintype "bidirectional"))
      (node (ref "U1") (pin "1") (pinfunction "VBAT_1") (pintype "power_in"))
    )
    (net (code "56") (name "Net-(JP54-P$1)") (class "Default")
      (node (ref "C14") (pin "1") (pinfunction "1_1") (pintype "passive"))
      (node (ref "JP54") (pin "1") (pinfunction "P$1_1") (pintype "bidirectional"))
      (node (ref "R2") (pin "1") (pinfunction "1_1") (pintype "passive"))
      (node (ref "S1") (pin "3") (pinfunction "3_3") (pintype "passive"))
      (node (ref "S1") (pin "4") (pinfunction "4_4") (pintype "passive"))
      (node (ref "U1") (pin "7") (pinfunction "NRST_7") (pintype "input"))
    )
    (net (code "57") (name "Net-(JP56-P$1)") (class "Default")
      (node (ref "JMP-ID") (pin "2") (pinfunction "2_2") (pintype "passive"))
      (node (ref "JP56") (pin "1") (pinfunction "P$1_1") (pintype "bidirectional"))
      (node (ref "USB") (pin "ID") (pinfunction "ID_ID") (pintype "bidirectional"))
    )
    (net (code "58") (name "Net-(JP57-P$1)") (class "Default")
      (node (ref "JP57") (pin "1") (pinfunction "P$1_1") (pintype "bidirectional"))
      (node (ref "JP66") (pin "4") (pinfunction "4_4") (pintype "passive"))
      (node (ref "U1") (pin "28") (pinfunction "BOOT1(PB2)_28") (pintype "input"))
    )
    (net (code "59") (name "Net-(JP58-P$1)") (class "Default")
      (node (ref "JP58") (pin "1") (pinfunction "P$1_1") (pintype "bidirectional"))
      (node (ref "R5") (pin "2") (pinfunction "2_2") (pintype "passive"))
      (node (ref "U1") (pin "44") (pinfunction "USB_DM(PA11)_44") (pintype "bidirectional"))
    )
    (net (code "60") (name "Net-(JP64-P$1)") (class "Default")
      (node (ref "JMP-VBUS") (pin "2") (pinfunction "2_2") (pintype "passive"))
      (node (ref "JP64") (pin "1") (pinfunction "P$1_1") (pintype "bidirectional"))
      (node (ref "U1") (pin "42") (pinfunction "VBUS(PA9)_42") (pintype "bidirectional"))
    )
    (net (code "61") (name "Net-(LED1-PadC)") (class "Default")
      (node (ref "LED1") (pin "C") (pinfunction "C_C") (pintype "passive"))
      (node (ref "R3") (pin "2") (pinfunction "2_2") (pintype "passive"))
    )
    (net (code "62") (name "Net-(Q1-B)") (class "Default")
      (node (ref "Q1") (pin "1") (pinfunction "B_1") (pintype "passive"))
      (node (ref "R7") (pin "2") (pinfunction "2_2") (pintype "passive"))
      (node (ref "R8") (pin "1") (pinfunction "1_1") (pintype "passive"))
    )
    (net (code "63") (name "Net-(Q1-C)") (class "Default")
      (node (ref "Q1") (pin "3") (pinfunction "C_3") (pintype "passive"))
      (node (ref "R6") (pin "2") (pinfunction "2_2") (pintype "passive"))
    )
    (net (code "64") (name "Net-(U1-BOOT0)") (class "Default")
      (node (ref "JP66") (pin "3") (pinfunction "3_3") (pintype "passive"))
      (node (ref "U1") (pin "60") (pinfunction "BOOT0_60") (pintype "input"))
    )
    (net (code "65") (name "Net-(U1-OSC_IN(PH0))") (class "Default")
      (node (ref "C12") (pin "1") (pinfunction "1_1") (pintype "passive"))
      (node (ref "U1") (pin "5") (pinfunction "OSC_IN(PH0)_5") (pintype "bidirectional"))
      (node (ref "Y1") (pin "3") (pinfunction "2_3") (pintype "passive"))
    )
    (net (code "66") (name "Net-(U1-OSC_OUT(PH1))") (class "Default")
      (node (ref "C13") (pin "1") (pinfunction "1_1") (pintype "passive"))
      (node (ref "U1") (pin "6") (pinfunction "OSC_OUT(PH1)_6") (pintype "bidirectional"))
      (node (ref "Y1") (pin "1") (pinfunction "1_1") (pintype "passive"))
    )
    (net (code "67") (name "Net-(U1-PB11)") (class "Default")
      (node (ref "C15") (pin "1") (pinfunction "1_1") (pintype "passive"))
      (node (ref "R10") (pin "2") (pinfunction "2_2") (pintype "passive"))
      (node (ref "U1") (pin "30") (pinfunction "PB11_30") (pintype "bidirectional"))
    )
    (net (code "68") (name "Net-(U1-VCAP_1)") (class "Default")
      (node (ref "C7") (pin "1") (pinfunction "1_1") (pintype "passive"))
      (node (ref "U1") (pin "31") (pinfunction "VCAP_1_31") (pintype "bidirectional"))
    )
    (net (code "69") (name "Net-(U1-VCAP_2)") (class "Default")
      (node (ref "C8") (pin "1") (pinfunction "1_1") (pintype "passive"))
      (node (ref "U1") (pin "47") (pinfunction "VCAP_2_47") (pintype "bidirectional"))
    )
    (net (code "70") (name "Net-(U1-VDDA)") (class "Default")
      (node (ref "C6") (pin "1") (pinfunction "1_1") (pintype "passive"))
      (node (ref "L1") (pin "1") (pinfunction "1_1") (pintype "passive"))
      (node (ref "U1") (pin "13") (pinfunction "VDDA_13") (pintype "power_in"))
    )
    (net (code "71") (name "Net-(U2-IO1)") (class "Default")
      (node (ref "R4") (pin "1") (pinfunction "1_1") (pintype "passive"))
      (node (ref "U2") (pin "2") (pinfunction "IO1_2") (pintype "bidirectional"))
      (node (ref "USB") (pin "D+") (pinfunction "D+_D+") (pintype "bidirectional"))
    )
    (net (code "72") (name "Net-(U2-IO2)") (class "Default")
      (node (ref "R5") (pin "1") (pinfunction "1_1") (pintype "passive"))
      (node (ref "U2") (pin "3") (pinfunction "IO2_3") (pintype "bidirectional"))
      (node (ref "USB") (pin "D-") (pinfunction "D-_D-") (pintype "bidirectional"))
    )
    (net (code "73") (name "Net-(U2-VCC)") (class "Default")
      (node (ref "C17") (pin "1") (pinfunction "1_1") (pintype "passive"))
      (node (ref "L2") (pin "1") (pinfunction "1_1") (pintype "passive"))
      (node (ref "U2") (pin "4") (pinfunction "VCC_4") (pintype "bidirectional"))
      (node (ref "USB") (pin "VBUS") (pinfunction "VBUS_VBUS") (pintype "bidirectional"))
    )
  )
)
